# radio.net
KiCad netlist of a schematic drawn in Altium Designer
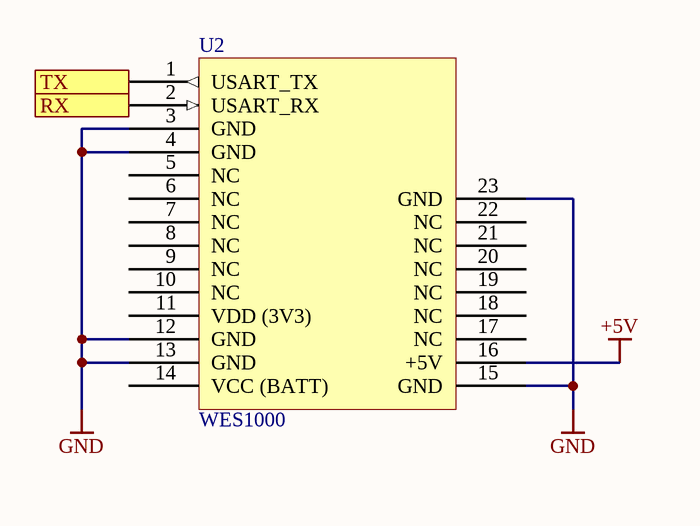
[diagram p0: radio.SchDoc]

(export (version "E")
  (design (tool "Eeschema 10.0.6"))
  (components
    (comp (ref "U2")
      (value "WES1000")
      (footprint "FP_WES1000")
      (description "SiLabs vezeték nélküli modul")
      (libsource (lib "hallglib") (part "WES1000"))
    )
  )
  (nets
    (net (code "1") (name "+5V") (class "Default")
      (node (ref "U2") (pin "16") (pinfunction "+5V_16") (pintype "passive"))
    )
    (net (code "2") (name "/RX") (class "Default")
      (node (ref "U2") (pin "2") (pinfunction "USART_RX_2") (pintype "input"))
    )
    (net (code "3") (name "/TX") (class "Default")
      (node (ref "U2") (pin "1") (pinfunction "USART_TX_1") (pintype "output"))
    )
    (net (code "4") (name "GND") (class "Default")
      (node (ref "U2") (pin "12") (pinfunction "GND_12") (pintype "passive"))
      (node (ref "U2") (pin "13") (pinfunction "GND_13") (pintype "passive"))
      (node (ref "U2") (pin "15") (pinfunction "GND_15") (pintype "passive"))
      (node (ref "U2") (pin "23") (pinfunction "GND_23") (pintype "passive"))
      (node (ref "U2") (pin "3") (pinfunction "GND_3") (pintype "passive"))
      (node (ref "U2") (pin "4") (pinfunction "GND_4") (pintype "passive"))
    )
    (net (code "5") (name "unconnected-(U2-NC-Pad5)") (class "Default")
      (node (ref "U2") (pin "5") (pinfunction "NC_5") (pintype "passive"))
    )
    (net (code "6") (name "unconnected-(U2-NC-Pad6)") (class "Default")
      (node (ref "U2") (pin "6") (pinfunction "NC_6") (pintype "passive"))
    )
    (net (code "7") (name "unconnected-(U2-NC-Pad7)") (class "Default")
      (node (ref "U2") (pin "7") (pinfunction "NC_7") (pintype "passive"))
    )
    (net (code "8") (name "unconnected-(U2-NC-Pad8)") (class "Default")
      (node (ref "U2") (pin "8") (pinfunction "NC_8") (pintype "passive"))
    )
    (net (code "9") (name "unconnected-(U2-NC-Pad9)") (class "Default")
      (node (ref "U2") (pin "9") (pinfunction "NC_9") (pintype "passive"))
    )
    (net (code "10") (name "unconnected-(U2-NC-Pad10)") (class "Default")
      (node (ref "U2") (pin "10") (pinfunction "NC_10") (pintype "passive"))
    )
    (net (code "11") (name "unconnected-(U2-NC-Pad17)") (class "Default")
      (node (ref "U2") (pin "17") (pinfunction "NC_17") (pintype "passive"))
    )
    (net (code "12") (name "unconnected-(U2-NC-Pad18)") (class "Default")
      (node (ref "U2") (pin "18") (pinfunction "NC_18") (pintype "passive"))
    )
    (net (code "13") (name "unconnected-(U2-NC-Pad19)") (class "Default")
      (node (ref "U2") (pin "19") (pinfunction "NC_19") (pintype "passive"))
    )
    (net (code "14") (name "unconnected-(U2-NC-Pad20)") (class "Default")
      (node (ref "U2") (pin "20") (pinfunction "NC_20") (pintype "passive"))
    )
    (net (code "15") (name "unconnected-(U2-NC-Pad21)") (class "Default")
      (node (ref "U2") (pin "21") (pinfunction "NC_21") (pintype "passive"))
    )
    (net (code "16") (name "unconnected-(U2-NC-Pad22)") (class "Default")
      (node (ref "U2") (pin "22") (pinfunction "NC_22") (pintype "passive"))
    )
    (net (code "17") (name "unconnected-(U2-VCC_(BATT)-Pad14)") (class "Default")
      (node (ref "U2") (pin "14") (pinfunction "VCC_(BATT)_14") (pintype "passive"))
    )
    (net (code "18") (name "unconnected-(U2-VDD_(3V3)-Pad11)") (class "Default")
      (node (ref "U2") (pin "11") (pinfunction "VDD_(3V3)_11") (pintype "passive"))
    )
  )
)
